# Sheet1.net
KiCad netlist of a schematic drawn in Altium Designer
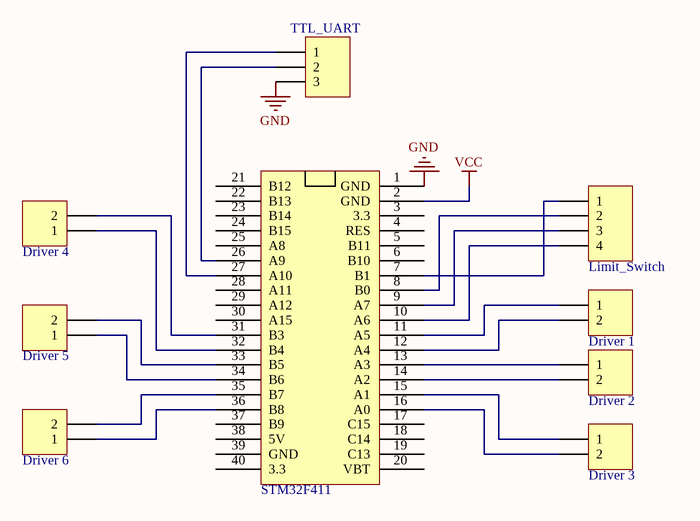
[diagram p0: Sheet1.SchDoc]

(export (version "E")
  (design (tool "Eeschema 10.0.6"))
  (components
    (comp (ref "*1")
      (value "STM32F411")
      (footprint "STM32F103")
      (libsource (lib "STM32F103") (part "STM32F103"))
    )
    (comp (ref "P1")
      (value "TTL_UART")
      (footprint "HDR1X3")
      (description "Header, 3-Pin")
      (fields (field (name "PUBLISHER") "Altium Limited"))
      (libsource (lib "Miscellaneous Connectors") (part "Header 3"))
    )
    (comp (ref "P2")
      (value "Limit_Switch")
      (footprint "HDR1X4")
      (description "Header, 4-Pin")
      (fields (field (name "PUBLISHER") "Altium Limited"))
      (libsource (lib "Miscellaneous Connectors") (part "Header 4"))
    )
    (comp (ref "P3")
      (value "Driver 4")
      (footprint "HDR1X2")
      (description "Header, 2-Pin")
      (fields (field (name "PUBLISHER") "Altium Limited"))
      (libsource (lib "Miscellaneous Connectors") (part "Header 2"))
    )
    (comp (ref "P4")
      (value "Driver 1")
      (footprint "HDR1X2")
      (description "Header, 2-Pin")
      (fields (field (name "PUBLISHER") "Altium Limited"))
      (libsource (lib "") (part "Header 2_1"))
    )
    (comp (ref "P5")
      (value "Driver 5")
      (footprint "HDR1X2")
      (description "Header, 2-Pin")
      (fields (field (name "PUBLISHER") "Altium Limited"))
      (libsource (lib "Miscellaneous Connectors") (part "Header 2"))
    )
    (comp (ref "P6")
      (value "Driver 2")
      (footprint "HDR1X2")
      (description "Header, 2-Pin")
      (fields (field (name "PUBLISHER") "Altium Limited"))
      (libsource (lib "") (part "Header 2_1"))
    )
    (comp (ref "P7")
      (value "Driver 6")
      (footprint "HDR1X2")
      (description "Header, 2-Pin")
      (fields (field (name "PUBLISHER") "Altium Limited"))
      (libsource (lib "Miscellaneous Connectors") (part "Header 2"))
    )
    (comp (ref "P8")
      (value "Driver 3")
      (footprint "HDR1X2")
      (description "Header, 2-Pin")
      (fields (field (name "PUBLISHER") "Altium Limited"))
      (libsource (lib "") (part "Header 2_1"))
    )
  )
  (nets
    (net (code "1") (name "GND") (class "Default")
      (node (ref "*1") (pin "1") (pinfunction "GND_1") (pintype "passive"))
      (node (ref "P1") (pin "3") (pinfunction "3_3") (pintype "passive"))
    )
    (net (code "2") (name "Net-(*1-A0)") (class "Default")
      (node (ref "*1") (pin "16") (pinfunction "A0_16") (pintype "passive"))
      (node (ref "P8") (pin "2") (pinfunction "2_2") (pintype "passive"))
    )
    (net (code "3") (name "Net-(*1-A1)") (class "Default")
      (node (ref "*1") (pin "15") (pinfunction "A1_15") (pintype "passive"))
      (node (ref "P8") (pin "1") (pinfunction "1_1") (pintype "passive"))
    )
    (net (code "4") (name "Net-(*1-A2)") (class "Default")
      (node (ref "*1") (pin "14") (pinfunction "A2_14") (pintype "passive"))
      (node (ref "P6") (pin "2") (pinfunction "2_2") (pintype "passive"))
    )
    (net (code "5") (name "Net-(*1-A3)") (class "Default")
      (node (ref "*1") (pin "13") (pinfunction "A3_13") (pintype "passive"))
      (node (ref "P6") (pin "1") (pinfunction "1_1") (pintype "passive"))
    )
    (net (code "6") (name "Net-(*1-A4)") (class "Default")
      (node (ref "*1") (pin "12") (pinfunction "A4_12") (pintype "passive"))
      (node (ref "P4") (pin "2") (pinfunction "2_2") (pintype "passive"))
    )
    (net (code "7") (name "Net-(*1-A5)") (class "Default")
      (node (ref "*1") (pin "11") (pinfunction "A5_11") (pintype "passive"))
      (node (ref "P4") (pin "1") (pinfunction "1_1") (pintype "passive"))
    )
    (net (code "8") (name "Net-(*1-A6)") (class "Default")
      (node (ref "*1") (pin "10") (pinfunction "A6_10") (pintype "passive"))
      (node (ref "P2") (pin "4") (pinfunction "4_4") (pintype "passive"))
    )
    (net (code "9") (name "Net-(*1-A7)") (class "Default")
      (node (ref "*1") (pin "9") (pinfunction "A7_9") (pintype "passive"))
      (node (ref "P2") (pin "3") (pinfunction "3_3") (pintype "passive"))
    )
    (net (code "10") (name "Net-(*1-A9)") (class "Default")
      (node (ref "*1") (pin "26") (pinfunction "A9_26") (pintype "passive"))
      (node (ref "P1") (pin "2") (pinfunction "2_2") (pintype "passive"))
    )
    (net (code "11") (name "Net-(*1-A10)") (class "Default")
      (node (ref "*1") (pin "27") (pinfunction "A10_27") (pintype "passive"))
      (node (ref "P1") (pin "1") (pinfunction "1_1") (pintype "passive"))
    )
    (net (code "12") (name "Net-(*1-B0)") (class "Default")
      (node (ref "*1") (pin "8") (pinfunction "B0_8") (pintype "passive"))
      (node (ref "P2") (pin "2") (pinfunction "2_2") (pintype "passive"))
    )
    (net (code "13") (name "Net-(*1-B1)") (class "Default")
      (node (ref "*1") (pin "7") (pinfunction "B1_7") (pintype "passive"))
      (node (ref "P2") (pin "1") (pinfunction "1_1") (pintype "passive"))
    )
    (net (code "14") (name "Net-(*1-B3)") (class "Default")
      (node (ref "*1") (pin "31") (pinfunction "B3_31") (pintype "passive"))
      (node (ref "P3") (pin "2") (pinfunction "2_2") (pintype "passive"))
    )
    (net (code "15") (name "Net-(*1-B4)") (class "Default")
      (node (ref "*1") (pin "32") (pinfunction "B4_32") (pintype "passive"))
      (node (ref "P3") (pin "1") (pinfunction "1_1") (pintype "passive"))
    )
    (net (code "16") (name "Net-(*1-B5)") (class "Default")
      (node (ref "*1") (pin "33") (pinfunction "B5_33") (pintype "passive"))
      (node (ref "P5") (pin "2") (pinfunction "2_2") (pintype "passive"))
    )
    (net (code "17") (name "Net-(*1-B6)") (class "Default")
      (node (ref "*1") (pin "34") (pinfunction "B6_34") (pintype "passive"))
      (node (ref "P5") (pin "1") (pinfunction "1_1") (pintype "passive"))
    )
    (net (code "18") (name "Net-(*1-B7)") (class "Default")
      (node (ref "*1") (pin "35") (pinfunction "B7_35") (pintype "passive"))
      (node (ref "P7") (pin "2") (pinfunction "2_2") (pintype "passive"))
    )
    (net (code "19") (name "Net-(*1-B8)") (class "Default")
      (node (ref "*1") (pin "36") (pinfunction "B8_36") (pintype "passive"))
      (node (ref "P7") (pin "1") (pinfunction "1_1") (pintype "passive"))
    )
    (net (code "20") (name "VCC") (class "Default")
      (node (ref "*1") (pin "2") (pinfunction "GND_2") (pintype "passive"))
    )
    (net (code "21") (name "unconnected-(*1-3.3-Pad3)") (class "Default")
      (node (ref "*1") (pin "3") (pinfunction "3.3_3") (pintype "passive"))
    )
    (net (code "22") (name "unconnected-(*1-3.3-Pad40)") (class "Default")
      (node (ref "*1") (pin "40") (pinfunction "3.3_40") (pintype "passive"))
    )
    (net (code "23") (name "unconnected-(*1-5V-Pad38)") (class "Default")
      (node (ref "*1") (pin "38") (pinfunction "5V_38") (pintype "passive"))
    )
    (net (code "24") (name "unconnected-(*1-A8-Pad25)") (class "Default")
      (node (ref "*1") (pin "25") (pinfunction "A8_25") (pintype "passive"))
    )
    (net (code "25") (name "unconnected-(*1-A11-Pad28)") (class "Default")
      (node (ref "*1") (pin "28") (pinfunction "A11_28") (pintype "passive"))
    )
    (net (code "26") (name "unconnected-(*1-A12-Pad29)") (class "Default")
      (node (ref "*1") (pin "29") (pinfunction "A12_29") (pintype "passive"))
    )
    (net (code "27") (name "unconnected-(*1-A15-Pad30)") (class "Default")
      (node (ref "*1") (pin "30") (pinfunction "A15_30") (pintype "passive"))
    )
    (net (code "28") (name "unconnected-(*1-B9-Pad37)") (class "Default")
      (node (ref "*1") (pin "37") (pinfunction "B9_37") (pintype "passive"))
    )
    (net (code "29") (name "unconnected-(*1-B10-Pad6)") (class "Default")
      (node (ref "*1") (pin "6") (pinfunction "B10_6") (pintype "passive"))
    )
    (net (code "30") (name "unconnected-(*1-B11-Pad5)") (class "Default")
      (node (ref "*1") (pin "5") (pinfunction "B11_5") (pintype "passive"))
    )
    (net (code "31") (name "unconnected-(*1-B12-Pad21)") (class "Default")
      (node (ref "*1") (pin "21") (pinfunction "B12_21") (pintype "passive"))
    )
    (net (code "32") (name "unconnected-(*1-B13-Pad22)") (class "Default")
      (node (ref "*1") (pin "22") (pinfunction "B13_22") (pintype "passive"))
    )
    (net (code "33") (name "unconnected-(*1-B14-Pad23)") (class "Default")
      (node (ref "*1") (pin "23") (pinfunction "B14_23") (pintype "passive"))
    )
    (net (code "34") (name "unconnected-(*1-B15-Pad24)") (class "Default")
      (node (ref "*1") (pin "24") (pinfunction "B15_24") (pintype "passive"))
    )
    (net (code "35") (name "unconnected-(*1-C13-Pad19)") (class "Default")
      (node (ref "*1") (pin "19") (pinfunction "C13_19") (pintype "passive"))
    )
    (net (code "36") (name "unconnected-(*1-C14-Pad18)") (class "Default")
      (node (ref "*1") (pin "18") (pinfunction "C14_18") (pintype "passive"))
    )
    (net (code "37") (name "unconnected-(*1-C15-Pad17)") (class "Default")
      (node (ref "*1") (pin "17") (pinfunction "C15_17") (pintype "passive"))
    )
    (net (code "38") (name "unconnected-(*1-GND-Pad39)") (class "Default")
      (node (ref "*1") (pin "39") (pinfunction "GND_39") (pintype "passive"))
    )
    (net (code "39") (name "unconnected-(*1-RES-Pad4)") (class "Default")
      (node (ref "*1") (pin "4") (pinfunction "RES_4") (pintype "passive"))
    )
    (net (code "40") (name "unconnected-(*1-VBT-Pad20)") (class "Default")
      (node (ref "*1") (pin "20") (pinfunction "VBT_20") (pintype "passive"))
    )
  )
)
